# power_v2.net
KiCad netlist of a schematic drawn in EAGLE
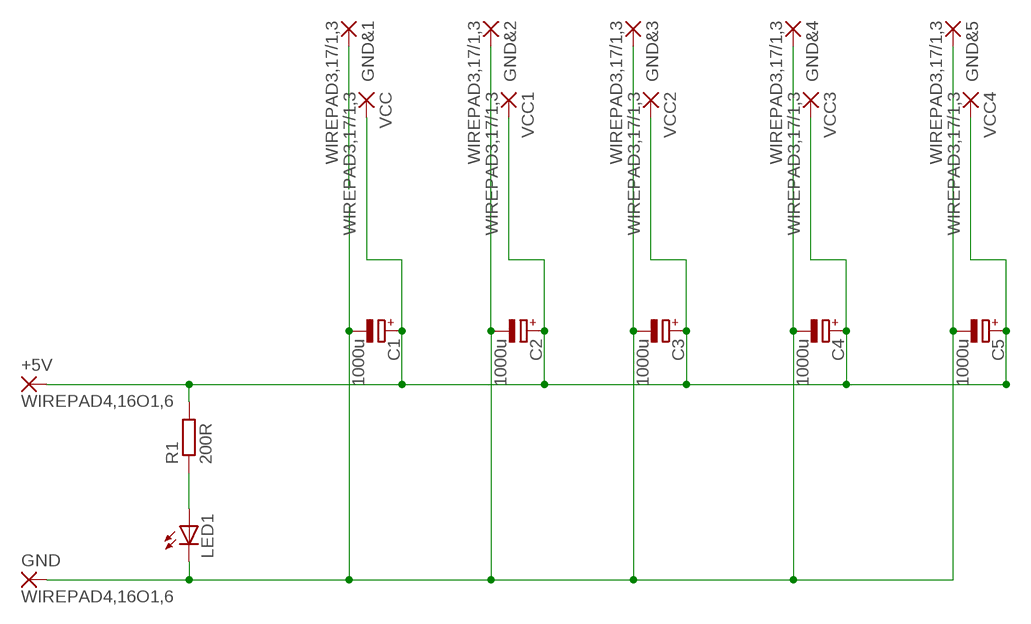
[diagram p0: schematic, sheet 1]

(export (version "E")
  (design (tool "Eeschema 10.0.6"))
  (components
    (comp (ref "+5V")
      (value "WIREPAD4,16O1,6")
      (footprint "eagle-import:4,16O1,6")
      (libsource (lib "eagle-import") (part "WIREPAD4,16O1,6"))
    )
    (comp (ref "C1")
      (value "1000u")
      (footprint "eagle-import:E5-10,5")
      (libsource (lib "eagle-import") (part "CPOL-EUE5-10.5"))
    )
    (comp (ref "C2")
      (value "1000u")
      (footprint "eagle-import:E5-10,5")
      (libsource (lib "eagle-import") (part "CPOL-EUE5-10.5"))
    )
    (comp (ref "C3")
      (value "1000u")
      (footprint "eagle-import:E5-10,5")
      (libsource (lib "eagle-import") (part "CPOL-EUE5-10.5"))
    )
    (comp (ref "C4")
      (value "1000u")
      (footprint "eagle-import:E5-10,5")
      (libsource (lib "eagle-import") (part "CPOL-EUE5-10.5"))
    )
    (comp (ref "C5")
      (value "1000u")
      (footprint "eagle-import:E5-10,5")
      (libsource (lib "eagle-import") (part "CPOL-EUE5-10.5"))
    )
    (comp (ref "GND")
      (value "WIREPAD4,16O1,6")
      (footprint "eagle-import:4,16O1,6")
      (libsource (lib "eagle-import") (part "WIREPAD4,16O1,6"))
    )
    (comp (ref "GND&1")
      (value "WIREPAD3,17/1,3")
      (footprint "eagle-import:3,17_1,3")
      (libsource (lib "eagle-import") (part "WIREPAD3,17/1,3"))
    )
    (comp (ref "GND&2")
      (value "WIREPAD3,17/1,3")
      (footprint "eagle-import:3,17_1,3")
      (libsource (lib "eagle-import") (part "WIREPAD3,17/1,3"))
    )
    (comp (ref "GND&3")
      (value "WIREPAD3,17/1,3")
      (footprint "eagle-import:3,17_1,3")
      (libsource (lib "eagle-import") (part "WIREPAD3,17/1,3"))
    )
    (comp (ref "GND&4")
      (value "WIREPAD3,17/1,3")
      (footprint "eagle-import:3,17_1,3")
      (libsource (lib "eagle-import") (part "WIREPAD3,17/1,3"))
    )
    (comp (ref "GND&5")
      (value "WIREPAD3,17/1,3")
      (footprint "eagle-import:3,17_1,3")
      (libsource (lib "eagle-import") (part "WIREPAD3,17/1,3"))
    )
    (comp (ref "LED1")
      (value "LED5MM")
      (footprint "eagle-import:LED5MM")
      (libsource (lib "eagle-import") (part "LED5MM"))
    )
    (comp (ref "R1")
      (value "200R")
      (footprint "eagle-import:R1206")
      (libsource (lib "eagle-import") (part "R-EU_R1206"))
    )
    (comp (ref "VCC")
      (value "WIREPAD3,17/1,3")
      (footprint "eagle-import:3,17_1,3")
      (libsource (lib "eagle-import") (part "WIREPAD3,17/1,3"))
    )
    (comp (ref "VCC1")
      (value "WIREPAD3,17/1,3")
      (footprint "eagle-import:3,17_1,3")
      (libsource (lib "eagle-import") (part "WIREPAD3,17/1,3"))
    )
    (comp (ref "VCC2")
      (value "WIREPAD3,17/1,3")
      (footprint "eagle-import:3,17_1,3")
      (libsource (lib "eagle-import") (part "WIREPAD3,17/1,3"))
    )
    (comp (ref "VCC3")
      (value "WIREPAD3,17/1,3")
      (footprint "eagle-import:3,17_1,3")
      (libsource (lib "eagle-import") (part "WIREPAD3,17/1,3"))
    )
    (comp (ref "VCC4")
      (value "WIREPAD3,17/1,3")
      (footprint "eagle-import:3,17_1,3")
      (libsource (lib "eagle-import") (part "WIREPAD3,17/1,3"))
    )
  )
  (nets
    (net (code "1") (name "Net-(+5V-P)") (class "Default")
      (node (ref "+5V") (pin "1") (pinfunction "P_1") (pintype "passive"))
      (node (ref "C1") (pin "+") (pinfunction "+_+") (pintype "passive"))
      (node (ref "C2") (pin "+") (pinfunction "+_+") (pintype "passive"))
      (node (ref "C3") (pin "+") (pinfunction "+_+") (pintype "passive"))
      (node (ref "C4") (pin "+") (pinfunction "+_+") (pintype "passive"))
      (node (ref "C5") (pin "+") (pinfunction "+_+") (pintype "passive"))
      (node (ref "R1") (pin "2") (pinfunction "2_2") (pintype "passive"))
      (node (ref "VCC") (pin "1") (pinfunction "P_1") (pintype "passive"))
      (node (ref "VCC1") (pin "1") (pinfunction "P_1") (pintype "passive"))
      (node (ref "VCC2") (pin "1") (pinfunction "P_1") (pintype "passive"))
      (node (ref "VCC3") (pin "1") (pinfunction "P_1") (pintype "passive"))
      (node (ref "VCC4") (pin "1") (pinfunction "P_1") (pintype "passive"))
    )
    (net (code "2") (name "Net-(GND&2-P)") (class "Default")
      (node (ref "C1") (pin "-") (pinfunction "-_-") (pintype "passive"))
      (node (ref "C2") (pin "-") (pinfunction "-_-") (pintype "passive"))
      (node (ref "C3") (pin "-") (pinfunction "-_-") (pintype "passive"))
      (node (ref "C4") (pin "-") (pinfunction "-_-") (pintype "passive"))
      (node (ref "C5") (pin "-") (pinfunction "-_-") (pintype "passive"))
      (node (ref "GND") (pin "1") (pinfunction "P_1") (pintype "passive"))
      (node (ref "GND&2") (pin "1") (pinfunction "P_1") (pintype "passive"))
      (node (ref "GND&3") (pin "1") (pinfunction "P_1") (pintype "passive"))
      (node (ref "GND&4") (pin "1") (pinfunction "P_1") (pintype "passive"))
      (node (ref "GND&5") (pin "1") (pinfunction "P_1") (pintype "passive"))
      (node (ref "LED1") (pin "K") (pinfunction "C_K") (pintype "passive"))
    )
    (net (code "3") (name "Net-(LED1-PadA)") (class "Default")
      (node (ref "LED1") (pin "A") (pinfunction "A_A") (pintype "passive"))
      (node (ref "R1") (pin "1") (pinfunction "1_1") (pintype "passive"))
    )
    (net (code "4") (name "unconnected-(GND&1-P-Pad1)") (class "Default")
      (node (ref "GND&1") (pin "1") (pinfunction "P_1") (pintype "passive"))
    )
  )
)
